# Snippet_TPIC6B595D.net
KiCad netlist of a schematic drawn in Altium Designer
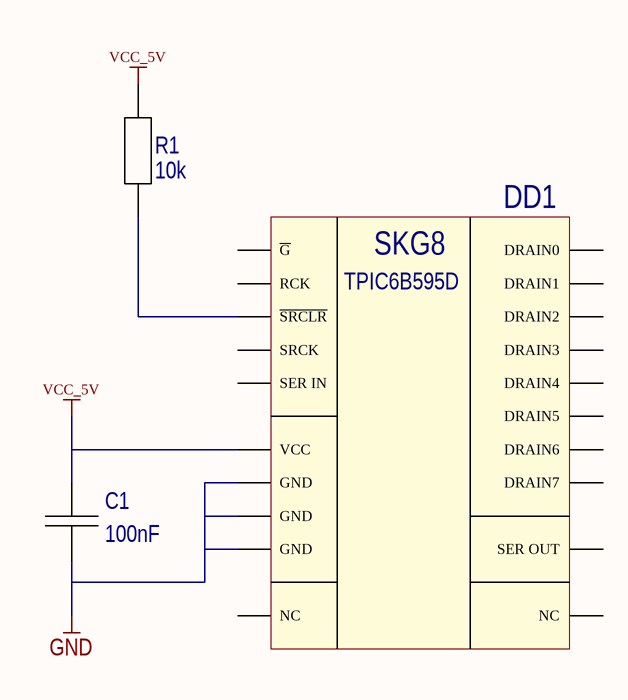
[diagram p0: Snippet_TPIC6B595D.SchDoc]

(export (version "E")
  (design (tool "Eeschema 10.0.6"))
  (components
    (comp (ref "C1")
      (value "100nF")
      (footprint "Capacitor_0805")
      (libsource (lib "Библиотека элементов") (part "Capacitor_0805"))
    )
    (comp (ref "DD1")
      (value "TPIC6B595D")
      (footprint "SOIC-20")
      (libsource (lib "Библиотека элементов") (part "TPIC6B595D"))
    )
    (comp (ref "R1")
      (value "10k")
      (footprint "RESISTOR_SMD0805")
      (libsource (lib "Библиотека элементов") (part "Resistor_0805"))
    )
  )
  (nets
    (net (code "1") (name "GND") (class "Default")
      (node (ref "C1") (pin "1") (pinfunction "1_1") (pintype "passive"))
      (node (ref "DD1") (pin "10") (pinfunction "GND_10") (pintype "passive"))
      (node (ref "DD1") (pin "11") (pinfunction "GND_11") (pintype "passive"))
      (node (ref "DD1") (pin "19") (pinfunction "GND_19") (pintype "passive"))
    )
    (net (code "2") (name "Net-(DD1-~{SRCLR})") (class "Default")
      (node (ref "DD1") (pin "8") (pinfunction "~{SRCLR}_8") (pintype "passive"))
      (node (ref "R1") (pin "1") (pinfunction "1_1") (pintype "passive"))
    )
    (net (code "3") (name "VCC_5V") (class "Default")
      (node (ref "C1") (pin "2") (pinfunction "2_2") (pintype "passive"))
      (node (ref "DD1") (pin "2") (pinfunction "VCC_2") (pintype "passive"))
      (node (ref "R1") (pin "2") (pinfunction "2_2") (pintype "passive"))
    )
    (net (code "4") (name "unconnected-(DD1-DRAIN0-Pad4)") (class "Default")
      (node (ref "DD1") (pin "4") (pinfunction "DRAIN0_4") (pintype "passive"))
    )
    (net (code "5") (name "unconnected-(DD1-DRAIN1-Pad5)") (class "Default")
      (node (ref "DD1") (pin "5") (pinfunction "DRAIN1_5") (pintype "passive"))
    )
    (net (code "6") (name "unconnected-(DD1-DRAIN2-Pad6)") (class "Default")
      (node (ref "DD1") (pin "6") (pinfunction "DRAIN2_6") (pintype "passive"))
    )
    (net (code "7") (name "unconnected-(DD1-DRAIN3-Pad7)") (class "Default")
      (node (ref "DD1") (pin "7") (pinfunction "DRAIN3_7") (pintype "passive"))
    )
    (net (code "8") (name "unconnected-(DD1-DRAIN4-Pad14)") (class "Default")
      (node (ref "DD1") (pin "14") (pinfunction "DRAIN4_14") (pintype "passive"))
    )
    (net (code "9") (name "unconnected-(DD1-DRAIN5-Pad15)") (class "Default")
      (node (ref "DD1") (pin "15") (pinfunction "DRAIN5_15") (pintype "passive"))
    )
    (net (code "10") (name "unconnected-(DD1-DRAIN6-Pad16)") (class "Default")
      (node (ref "DD1") (pin "16") (pinfunction "DRAIN6_16") (pintype "passive"))
    )
    (net (code "11") (name "unconnected-(DD1-DRAIN7-Pad17)") (class "Default")
      (node (ref "DD1") (pin "17") (pinfunction "DRAIN7_17") (pintype "passive"))
    )
    (net (code "12") (name "unconnected-(DD1-NC-Pad1)") (class "Default")
      (node (ref "DD1") (pin "1") (pinfunction "NC_1") (pintype "passive"))
    )
    (net (code "13") (name "unconnected-(DD1-NC-Pad20)") (class "Default")
      (node (ref "DD1") (pin "20") (pinfunction "NC_20") (pintype "passive"))
    )
    (net (code "14") (name "unconnected-(DD1-RCK-Pad12)") (class "Default")
      (node (ref "DD1") (pin "12") (pinfunction "RCK_12") (pintype "passive"))
    )
    (net (code "15") (name "unconnected-(DD1-SER_IN-Pad3)") (class "Default")
      (node (ref "DD1") (pin "3") (pinfunction "SER_IN_3") (pintype "passive"))
    )
    (net (code "16") (name "unconnected-(DD1-SER_OUT-Pad18)") (class "Default")
      (node (ref "DD1") (pin "18") (pinfunction "SER_OUT_18") (pintype "passive"))
    )
    (net (code "17") (name "unconnected-(DD1-SRCK-Pad13)") (class "Default")
      (node (ref "DD1") (pin "13") (pinfunction "SRCK_13") (pintype "passive"))
    )
    (net (code "18") (name "unconnected-(DD1-~{G}-Pad9)") (class "Default")
      (node (ref "DD1") (pin "9") (pinfunction "~{G}_9") (pintype "passive"))
    )
  )
)
